# GSMMHMUltraSlim.net
KiCad netlist of a schematic drawn in Altium Designer
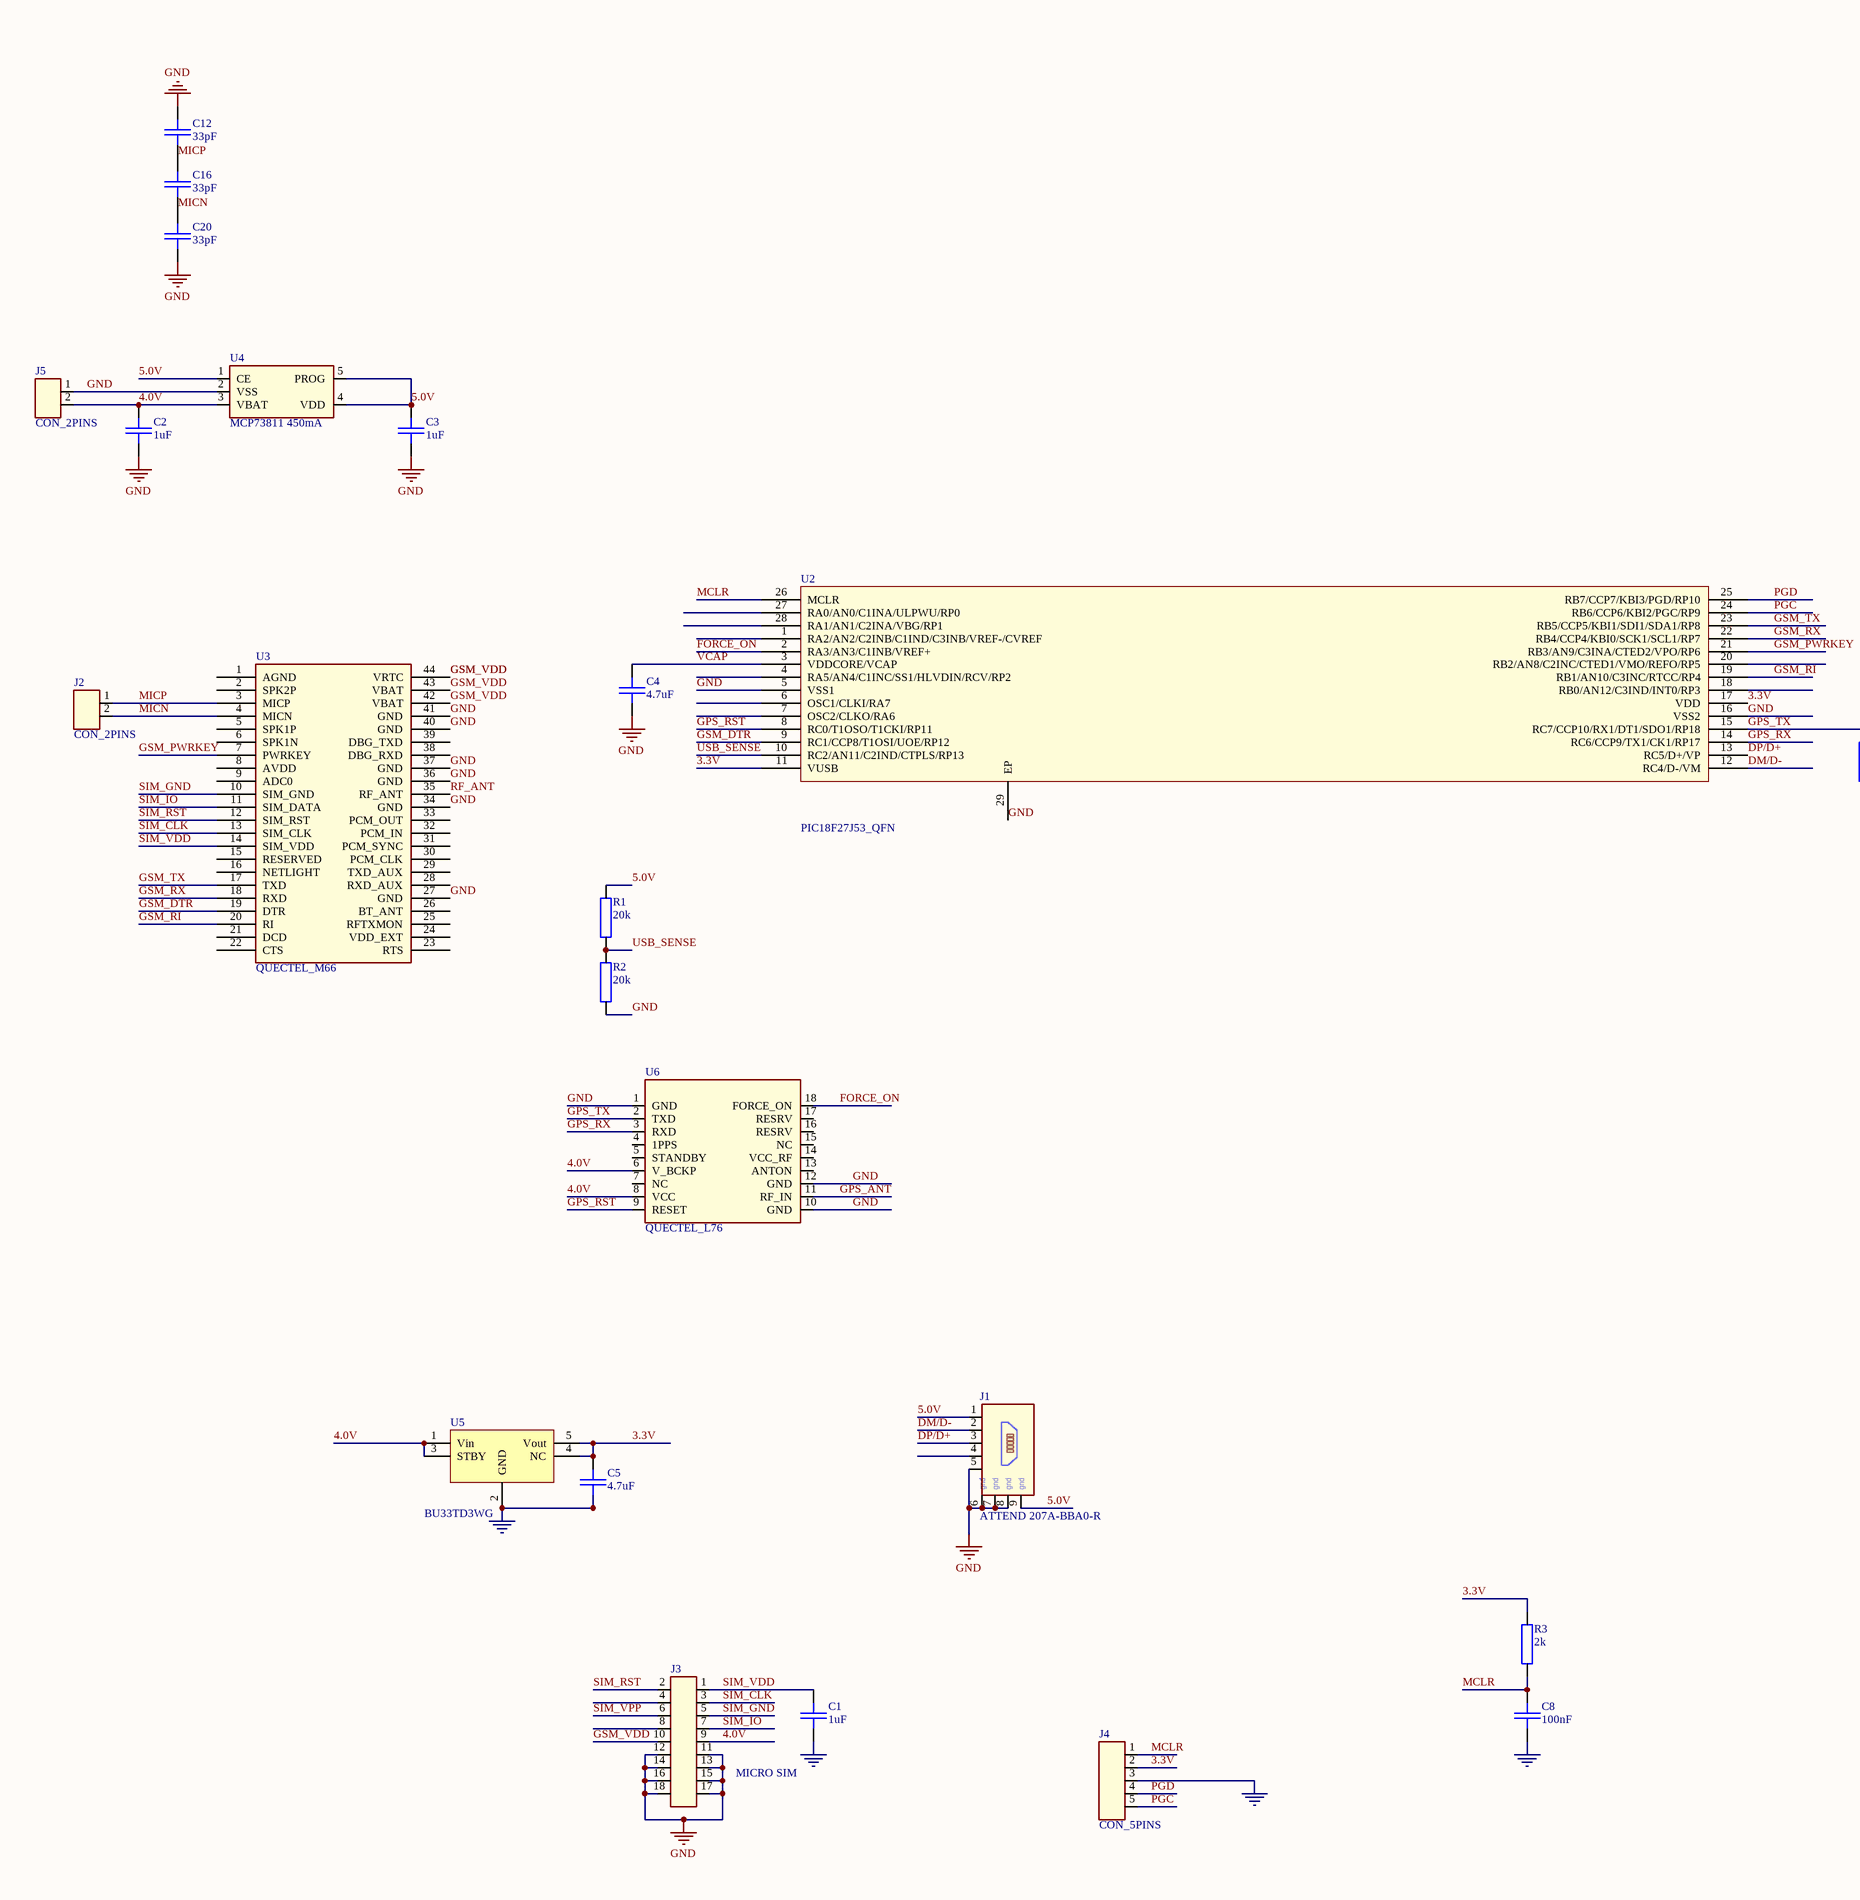
[diagram p0: GSMMHMUltraSlim.SchDoc, left]
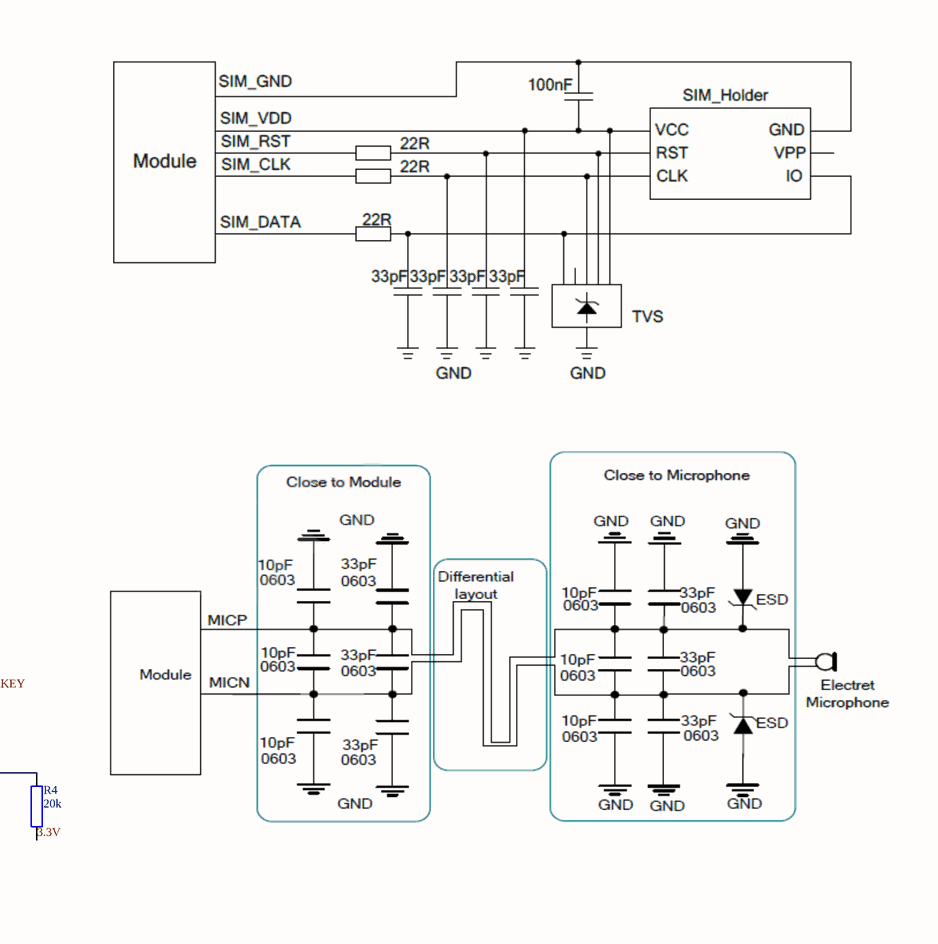
[diagram p1: GSMMHMUltraSlim.SchDoc, right]

(export (version "E")
  (design (tool "Eeschema 10.0.6"))
  (components
    (comp (ref "C1") (value "1uF") (footprint "SMD_0603_CAPC1608X95N") (libsource (lib "DLV") (part "C")))
    (comp (ref "C2") (value "1uF") (footprint "SMD_0603_CAPC1608X95N") (libsource (lib "DLV") (part "C")))
    (comp (ref "C3") (value "1uF") (footprint "SMD_0603_CAPC1608X95N") (libsource (lib "DLV") (part "C")))
    (comp (ref "C4") (value "4.7uF") (footprint "SMD_0603_CAPC1608X95N") (libsource (lib "DLV") (part "C")))
    (comp (ref "C5") (value "4.7uF") (footprint "SMD_0603_CAPC1608X95N") (libsource (lib "DLV") (part "C")))
    (comp (ref "C8") (value "100nF") (footprint "SMD_0603_CAPC1608X95N") (libsource (lib "DLV") (part "C")))
    (comp (ref "C12") (value "33pF") (footprint "SMD_0603_CAPC1608X95N") (libsource (lib "DLV") (part "C")))
    (comp (ref "C16") (value "33pF") (footprint "SMD_0603_CAPC1608X95N") (libsource (lib "DLV") (part "C")))
    (comp (ref "C20") (value "33pF") (footprint "SMD_0603_CAPC1608X95N") (libsource (lib "DLV") (part "C")))
    (comp (ref "J1")
      (value "ATTEND 207A-BBA0-R")
      (footprint "SMD_CON_MICRO_USB")
      (libsource (lib "DLV") (part "CON_USB_MINI"))
    )
    (comp (ref "J2") (value "CON_2PINS") (footprint "SMD_MIC_4MM") (libsource (lib "DLV") (part "CON_2PINS")))
    (comp (ref "J3")
      (value "MICRO SIM")
      (footprint "SMD_CON-WURTH_MICRO_SIM_693021010811")
      (libsource (lib "DLV") (part "CON_2ROWS_18PINS"))
    )
    (comp (ref "J4") (value "CON_5PINS") (footprint "SIP5 - PGM") (libsource (lib "DLV") (part "CON_5PINS")))
    (comp (ref "J5")
      (value "CON_2PINS")
      (footprint "PTH_HDRV02W64P254_1X02")
      (libsource (lib "DLV") (part "CON_2PINS"))
    )
    (comp (ref "R1") (value "20k") (footprint "SMD_0603_RESC1608X55N") (libsource (lib "DLV") (part "R")))
    (comp (ref "R2") (value "20k") (footprint "SMD_0603_RESC1608X55N") (libsource (lib "DLV") (part "R")))
    (comp (ref "R3") (value "2k") (footprint "SMD_0603_RESC1608X55N") (libsource (lib "DLV") (part "R")))
    (comp (ref "R4") (value "20k") (footprint "SMD_0603_RESC1608X55N") (libsource (lib "DLV") (part "R")))
    (comp (ref "U2")
      (value "PIC18F27J53_QFN")
      (footprint "SMD_QFN65P600X600X100-29AN")
      (libsource (lib "DLV") (part "IC_PIC18F27J53_QFN"))
    )
    (comp (ref "U3")
      (value "QUECTEL_M66")
      (footprint "SMD_MOD_M66-44N - NO UNUSED PINS")
      (libsource (lib "DLV") (part "MOD_QUECTEL_M66"))
    )
    (comp (ref "U4")
      (value "MCP73811 450mA")
      (footprint "SMD_SOT26_SOT95P285X140-5N - DLV")
      (description "MCP73812")
      (fields
        (field (name "DB_PART_NUMBER") "PSU000000127")
        (field (name "DB_MANUFACTURER_PART") "ROHM        BD33KA5WF-E2")
        (field (name "DB_APPROVED_BY") "VSN")
      )
      (libsource (lib "DLV") (part "IC_MCP73812"))
    )
    (comp (ref "U5")
      (value "BU33TD3WG")
      (footprint "SMD_SOT26_SOT95P285X140-5N - DLV")
      (libsource (lib "DLV") (part "IC_BU33TD3WG"))
    )
    (comp (ref "U6")
      (value "QUECTEL_L76")
      (footprint "SMD_MOD_L76_SOIC110P970X1010-18N - NO UNUSED PINS")
      (libsource (lib "DLV") (part "MOD_QUECTEL_L76"))
    )
  )
  (nets
    (net (code "1") (name "/3.3V") (class "Default")
      (node (ref "C5") (pin "1") (pinfunction "1_1") (pintype "passive"))
      (node (ref "J4") (pin "2") (pinfunction "2_2") (pintype "passive"))
      (node (ref "R3") (pin "1") (pinfunction "1_1") (pintype "passive"))
      (node (ref "R4") (pin "1") (pinfunction "1_1") (pintype "passive"))
      (node (ref "U2") (pin "11") (pinfunction "VUSB_11") (pintype "passive"))
      (node (ref "U2") (pin "17") (pinfunction "VDD_17") (pintype "passive"))
      (node (ref "U5") (pin "4") (pinfunction "NC_4") (pintype "passive"))
      (node (ref "U5") (pin "5") (pinfunction "Vout_5") (pintype "passive"))
    )
    (net (code "2") (name "/4.0V") (class "Default")
      (node (ref "C2") (pin "1") (pinfunction "1_1") (pintype "passive"))
      (node (ref "J3") (pin "9") (pinfunction "9_9") (pintype "passive"))
      (node (ref "J5") (pin "2") (pinfunction "2_2") (pintype "passive"))
      (node (ref "U4") (pin "3") (pinfunction "VBAT_3") (pintype "passive"))
      (node (ref "U5") (pin "1") (pinfunction "Vin_1") (pintype "passive"))
      (node (ref "U5") (pin "3") (pinfunction "STBY_3") (pintype "passive"))
      (node (ref "U6") (pin "6") (pinfunction "V_BCKP_6") (pintype "passive"))
      (node (ref "U6") (pin "8") (pinfunction "VCC_8") (pintype "passive"))
    )
    (net (code "3") (name "/5.0V") (class "Default")
      (node (ref "C3") (pin "1") (pinfunction "1_1") (pintype "passive"))
      (node (ref "J1") (pin "1") (pinfunction "1_1") (pintype "passive"))
      (node (ref "J1") (pin "9") (pinfunction "9_9") (pintype "passive"))
      (node (ref "R1") (pin "2") (pinfunction "2_2") (pintype "passive"))
      (node (ref "U4") (pin "1") (pinfunction "CE_1") (pintype "passive"))
      (node (ref "U4") (pin "4") (pinfunction "VDD_4") (pintype "passive"))
      (node (ref "U4") (pin "5") (pinfunction "PROG_5") (pintype "passive"))
    )
    (net (code "4") (name "/DM{slash}D-") (class "Default")
      (node (ref "J1") (pin "2") (pinfunction "2_2") (pintype "passive"))
      (node (ref "U2") (pin "12") (pinfunction "RC4/D-/VM_12") (pintype "passive"))
    )
    (net (code "5") (name "/DP{slash}D+") (class "Default")
      (node (ref "J1") (pin "3") (pinfunction "3_3") (pintype "passive"))
      (node (ref "U2") (pin "13") (pinfunction "RC5/D+/VP_13") (pintype "passive"))
    )
    (net (code "6") (name "/FORCE_ON") (class "Default")
      (node (ref "U2") (pin "2") (pinfunction "RA3/AN3/C1INB/VREF+_2") (pintype "passive"))
      (node (ref "U6") (pin "18") (pinfunction "FORCE_ON_18") (pintype "passive"))
    )
    (net (code "7") (name "/GPS_ANT") (class "Default")
      (node (ref "U6") (pin "11") (pinfunction "RF_IN_11") (pintype "passive"))
    )
    (net (code "8") (name "/GPS_RST") (class "Default")
      (node (ref "U2") (pin "8") (pinfunction "RC0/T1OSO/T1CKI/RP11_8") (pintype "passive"))
      (node (ref "U6") (pin "9") (pinfunction "RESET_9") (pintype "passive"))
    )
    (net (code "9") (name "/GPS_RX") (class "Default")
      (node (ref "U2") (pin "14") (pinfunction "RC6/CCP9/TX1/CK1/RP17_14") (pintype "passive"))
      (node (ref "U6") (pin "3") (pinfunction "RXD_3") (pintype "passive"))
    )
    (net (code "10") (name "/GPS_TX") (class "Default")
      (node (ref "R4") (pin "2") (pinfunction "2_2") (pintype "passive"))
      (node (ref "U2") (pin "15") (pinfunction "RC7/CCP10/RX1/DT1/SDO1/RP18_15") (pintype "passive"))
      (node (ref "U6") (pin "2") (pinfunction "TXD_2") (pintype "passive"))
    )
    (net (code "11") (name "/GSM_DTR") (class "Default")
      (node (ref "U2") (pin "9") (pinfunction "RC1/CCP8/T1OSI/UOE/RP12_9") (pintype "passive"))
      (node (ref "U3") (pin "19") (pinfunction "DTR_19") (pintype "passive"))
    )
    (net (code "12") (name "/GSM_PWRKEY") (class "Default")
      (node (ref "U2") (pin "21") (pinfunction "RB3/AN9/C3INA/CTED2/VPO/RP6_21") (pintype "passive"))
      (node (ref "U3") (pin "7") (pinfunction "PWRKEY_7") (pintype "passive"))
    )
    (net (code "13") (name "/GSM_RI") (class "Default")
      (node (ref "U2") (pin "19") (pinfunction "RB1/AN10/C3INC/RTCC/RP4_19") (pintype "passive"))
      (node (ref "U3") (pin "20") (pinfunction "RI_20") (pintype "passive"))
    )
    (net (code "14") (name "/GSM_RX") (class "Default")
      (node (ref "U2") (pin "22") (pinfunction "RB4/CCP4/KBI0/SCK1/SCL1/RP7_22") (pintype "passive"))
      (node (ref "U3") (pin "18") (pinfunction "RXD_18") (pintype "passive"))
    )
    (net (code "15") (name "/GSM_TX") (class "Default")
      (node (ref "U2") (pin "23") (pinfunction "RB5/CCP5/KBI1/SDI1/SDA1/RP8_23") (pintype "passive"))
      (node (ref "U3") (pin "17") (pinfunction "TXD_17") (pintype "passive"))
    )
    (net (code "16") (name "/GSM_VDD") (class "Default")
      (node (ref "J3") (pin "10") (pinfunction "10_10") (pintype "passive"))
      (node (ref "U3") (pin "42") (pinfunction "VBAT_42") (pintype "passive"))
      (node (ref "U3") (pin "43") (pinfunction "VBAT_43") (pintype "passive"))
      (node (ref "U3") (pin "44") (pinfunction "VRTC_44") (pintype "passive"))
    )
    (net (code "17") (name "/MCLR") (class "Default")
      (node (ref "C8") (pin "1") (pinfunction "1_1") (pintype "passive"))
      (node (ref "J4") (pin "1") (pinfunction "1_1") (pintype "passive"))
      (node (ref "R3") (pin "2") (pinfunction "2_2") (pintype "passive"))
      (node (ref "U2") (pin "26") (pinfunction "MCLR_26") (pintype "passive"))
    )
    (net (code "18") (name "/MICN") (class "Default")
      (node (ref "C16") (pin "2") (pinfunction "2_2") (pintype "passive"))
      (node (ref "C20") (pin "1") (pinfunction "1_1") (pintype "passive"))
      (node (ref "J2") (pin "2") (pinfunction "2_2") (pintype "passive"))
      (node (ref "U3") (pin "4") (pinfunction "MICN_4") (pintype "passive"))
    )
    (net (code "19") (name "/MICP") (class "Default")
      (node (ref "C12") (pin "2") (pinfunction "2_2") (pintype "passive"))
      (node (ref "C16") (pin "1") (pinfunction "1_1") (pintype "passive"))
      (node (ref "J2") (pin "1") (pinfunction "1_1") (pintype "passive"))
      (node (ref "U3") (pin "3") (pinfunction "MICP_3") (pintype "passive"))
    )
    (net (code "20") (name "/PGC") (class "Default")
      (node (ref "J4") (pin "5") (pinfunction "5_5") (pintype "passive"))
      (node (ref "U2") (pin "24") (pinfunction "RB6/CCP6/KBI2/PGC/RP9_24") (pintype "passive"))
    )
    (net (code "21") (name "/PGD") (class "Default")
      (node (ref "J4") (pin "4") (pinfunction "4_4") (pintype "passive"))
      (node (ref "U2") (pin "25") (pinfunction "RB7/CCP7/KBI3/PGD/RP10_25") (pintype "passive"))
    )
    (net (code "22") (name "/RF_ANT") (class "Default")
      (node (ref "U3") (pin "35") (pinfunction "RF_ANT_35") (pintype "passive"))
    )
    (net (code "23") (name "/SIM_CLK") (class "Default")
      (node (ref "J3") (pin "3") (pinfunction "3_3") (pintype "passive"))
      (node (ref "U3") (pin "13") (pinfunction "SIM_CLK_13") (pintype "passive"))
    )
    (net (code "24") (name "/SIM_GND") (class "Default")
      (node (ref "J3") (pin "5") (pinfunction "5_5") (pintype "passive"))
      (node (ref "U3") (pin "10") (pinfunction "SIM_GND_10") (pintype "passive"))
    )
    (net (code "25") (name "/SIM_IO") (class "Default")
      (node (ref "J3") (pin "7") (pinfunction "7_7") (pintype "passive"))
      (node (ref "U3") (pin "11") (pinfunction "SIM_DATA_11") (pintype "passive"))
    )
    (net (code "26") (name "/SIM_RST") (class "Default")
      (node (ref "J3") (pin "2") (pinfunction "2_2") (pintype "passive"))
      (node (ref "U3") (pin "12") (pinfunction "SIM_RST_12") (pintype "passive"))
    )
    (net (code "27") (name "/SIM_VDD") (class "Default")
      (node (ref "C1") (pin "1") (pinfunction "1_1") (pintype "passive"))
      (node (ref "J3") (pin "1") (pinfunction "1_1") (pintype "passive"))
      (node (ref "U3") (pin "14") (pinfunction "SIM_VDD_14") (pintype "passive"))
    )
    (net (code "28") (name "/SIM_VPP") (class "Default")
      (node (ref "J3") (pin "6") (pinfunction "6_6") (pintype "passive"))
    )
    (net (code "29") (name "/USB_SENSE") (class "Default")
      (node (ref "R1") (pin "1") (pinfunction "1_1") (pintype "passive"))
      (node (ref "R2") (pin "2") (pinfunction "2_2") (pintype "passive"))
      (node (ref "U2") (pin "10") (pinfunction "RC2/AN11/C2IND/CTPLS/RP13_10") (pintype "passive"))
    )
    (net (code "30") (name "/VCAP") (class "Default")
      (node (ref "C4") (pin "1") (pinfunction "1_1") (pintype "passive"))
      (node (ref "U2") (pin "3") (pinfunction "VDDCORE/VCAP_3") (pintype "passive"))
    )
    (net (code "31") (name "GND") (class "Default")
      (node (ref "C1") (pin "2") (pinfunction "2_2") (pintype "passive"))
      (node (ref "C12") (pin "1") (pinfunction "1_1") (pintype "passive"))
      (node (ref "C2") (pin "2") (pinfunction "2_2") (pintype "passive"))
      (node (ref "C20") (pin "2") (pinfunction "2_2") (pintype "passive"))
      (node (ref "C3") (pin "2") (pinfunction "2_2") (pintype "passive"))
      (node (ref "C4") (pin "2") (pinfunction "2_2") (pintype "passive"))
      (node (ref "C5") (pin "2") (pinfunction "2_2") (pintype "passive"))
      (node (ref "C8") (pin "2") (pinfunction "2_2") (pintype "passive"))
      (node (ref "J1") (pin "5") (pinfunction "5_5") (pintype "passive"))
      (node (ref "J1") (pin "6") (pinfunction "6_6") (pintype "passive"))
      (node (ref "J1") (pin "7") (pinfunction "7_7") (pintype "passive"))
      (node (ref "J1") (pin "8") (pinfunction "8_8") (pintype "passive"))
      (node (ref "J3") (pin "11") (pinfunction "11_11") (pintype "passive"))
      (node (ref "J3") (pin "12") (pinfunction "12_12") (pintype "passive"))
      (node (ref "J3") (pin "13") (pinfunction "13_13") (pintype "passive"))
      (node (ref "J3") (pin "14") (pinfunction "14_14") (pintype "passive"))
      (node (ref "J3") (pin "15") (pinfunction "15_15") (pintype "passive"))
      (node (ref "J3") (pin "16") (pinfunction "16_16") (pintype "passive"))
      (node (ref "J3") (pin "17") (pinfunction "17_17") (pintype "passive"))
      (node (ref "J3") (pin "18") (pinfunction "18_18") (pintype "passive"))
      (node (ref "J4") (pin "3") (pinfunction "3_3") (pintype "passive"))
      (node (ref "J5") (pin "1") (pinfunction "1_1") (pintype "passive"))
      (node (ref "R2") (pin "1") (pinfunction "1_1") (pintype "passive"))
      (node (ref "U2") (pin "16") (pinfunction "VSS2_16") (pintype "passive"))
      (node (ref "U2") (pin "29") (pinfunction "EP_29") (pintype "passive"))
      (node (ref "U2") (pin "5") (pinfunction "VSS1_5") (pintype "passive"))
      (node (ref "U3") (pin "27") (pinfunction "GND_27") (pintype "passive"))
      (node (ref "U3") (pin "34") (pinfunction "GND_34") (pintype "passive"))
      (node (ref "U3") (pin "36") (pinfunction "GND_36") (pintype "passive"))
      (node (ref "U3") (pin "37") (pinfunction "GND_37") (pintype "passive"))
      (node (ref "U3") (pin "40") (pinfunction "GND_40") (pintype "passive"))
      (node (ref "U3") (pin "41") (pinfunction "GND_41") (pintype "passive"))
      (node (ref "U4") (pin "2") (pinfunction "VSS_2") (pintype "passive"))
      (node (ref "U5") (pin "2") (pinfunction "GND_2") (pintype "passive"))
      (node (ref "U6") (pin "1") (pinfunction "GND_1") (pintype "passive"))
      (node (ref "U6") (pin "10") (pinfunction "GND_10") (pintype "passive"))
      (node (ref "U6") (pin "12") (pinfunction "GND_12") (pintype "passive"))
    )
    (net (code "32") (name "unconnected-(J1-Pad4)") (class "Default")
      (node (ref "J1") (pin "4") (pinfunction "4_4") (pintype "passive"))
    )
    (net (code "33") (name "unconnected-(J3-Pad4)") (class "Default")
      (node (ref "J3") (pin "4") (pinfunction "4_4") (pintype "passive"))
    )
    (net (code "34") (name "unconnected-(J3-Pad8)") (class "Default")
      (node (ref "J3") (pin "8") (pinfunction "8_8") (pintype "passive"))
    )
    (net (code "35") (name "unconnected-(U2-OSC1{slash}CLKI{slash}RA7-Pad6)") (class "Default")
      (node (ref "U2") (pin "6") (pinfunction "OSC1/CLKI/RA7_6") (pintype "passive"))
    )
    (net (code "36") (name "unconnected-(U2-OSC2{slash}CLKO{slash}RA6-Pad7)") (class "Default")
      (node (ref "U2") (pin "7") (pinfunction "OSC2/CLKO/RA6_7") (pintype "passive"))
    )
    (net (code "37") (name "unconnected-(U2-RA0{slash}AN0{slash}C1INA{slash}ULPWU{slash}RP0-Pad27)") (class "Default")
      (node (ref "U2") (pin "27") (pinfunction "RA0/AN0/C1INA/ULPWU/RP0_27") (pintype "passive"))
    )
    (net (code "38") (name "unconnected-(U2-RA1{slash}AN1{slash}C2INA{slash}VBG{slash}RP1-Pad28)") (class "Default")
      (node (ref "U2") (pin "28") (pinfunction "RA1/AN1/C2INA/VBG/RP1_28") (pintype "passive"))
    )
    (net (code "39") (name "unconnected-(U2-RA2{slash}AN2{slash}C2INB{slash}C1IND{slash}C3INB{slash}VREF-{slash}CVREF-Pad1)") (class "Default")
      (node (ref "U2") (pin "1") (pinfunction "RA2/AN2/C2INB/C1IND/C3INB/VREF-/CVREF_1") (pintype "passive"))
    )
    (net (code "40") (name "unconnected-(U2-RA5{slash}AN4{slash}C1INC{slash}SS1{slash}HLVDIN{slash}RCV{slash}RP2-Pad4)") (class "Default")
      (node (ref "U2") (pin "4") (pinfunction "RA5/AN4/C1INC/SS1/HLVDIN/RCV/RP2_4") (pintype "passive"))
    )
    (net (code "41") (name "unconnected-(U2-RB0{slash}AN12{slash}C3IND{slash}INT0{slash}RP3-Pad18)") (class "Default")
      (node (ref "U2") (pin "18") (pinfunction "RB0/AN12/C3IND/INT0/RP3_18") (pintype "passive"))
    )
    (net (code "42") (name "unconnected-(U2-RB2{slash}AN8{slash}C2INC{slash}CTED1{slash}VMO{slash}REFO{slash}RP5-Pad20)") (class "Default")
      (node (ref "U2") (pin "20") (pinfunction "RB2/AN8/C2INC/CTED1/VMO/REFO/RP5_20") (pintype "passive"))
    )
    (net (code "43") (name "unconnected-(U3-ADC0-Pad9)") (class "Default")
      (node (ref "U3") (pin "9") (pinfunction "ADC0_9") (pintype "passive"))
    )
    (net (code "44") (name "unconnected-(U3-AGND-Pad1)") (class "Default")
      (node (ref "U3") (pin "1") (pinfunction "AGND_1") (pintype "passive"))
    )
    (net (code "45") (name "unconnected-(U3-AVDD-Pad8)") (class "Default")
      (node (ref "U3") (pin "8") (pinfunction "AVDD_8") (pintype "passive"))
    )
    (net (code "46") (name "unconnected-(U3-BT_ANT-Pad26)") (class "Default")
      (node (ref "U3") (pin "26") (pinfunction "BT_ANT_26") (pintype "passive"))
    )
    (net (code "47") (name "unconnected-(U3-CTS-Pad22)") (class "Default")
      (node (ref "U3") (pin "22") (pinfunction "CTS_22") (pintype "passive"))
    )
    (net (code "48") (name "unconnected-(U3-DBG_RXD-Pad38)") (class "Default")
      (node (ref "U3") (pin "38") (pinfunction "DBG_RXD_38") (pintype "passive"))
    )
    (net (code "49") (name "unconnected-(U3-DBG_TXD-Pad39)") (class "Default")
      (node (ref "U3") (pin "39") (pinfunction "DBG_TXD_39") (pintype "passive"))
    )
    (net (code "50") (name "unconnected-(U3-DCD-Pad21)") (class "Default")
      (node (ref "U3") (pin "21") (pinfunction "DCD_21") (pintype "passive"))
    )
    (net (code "51") (name "unconnected-(U3-NETLIGHT-Pad16)") (class "Default")
      (node (ref "U3") (pin "16") (pinfunction "NETLIGHT_16") (pintype "passive"))
    )
    (net (code "52") (name "unconnected-(U3-PCM_CLK-Pad30)") (class "Default")
      (node (ref "U3") (pin "30") (pinfunction "PCM_CLK_30") (pintype "passive"))
    )
    (net (code "53") (name "unconnected-(U3-PCM_IN-Pad32)") (class "Default")
      (node (ref "U3") (pin "32") (pinfunction "PCM_IN_32") (pintype "passive"))
    )
    (net (code "54") (name "unconnected-(U3-PCM_OUT-Pad33)") (class "Default")
      (node (ref "U3") (pin "33") (pinfunction "PCM_OUT_33") (pintype "passive"))
    )
    (net (code "55") (name "unconnected-(U3-PCM_SYNC-Pad31)") (class "Default")
      (node (ref "U3") (pin "31") (pinfunction "PCM_SYNC_31") (pintype "passive"))
    )
    (net (code "56") (name "unconnected-(U3-RESERVED-Pad15)") (class "Default")
      (node (ref "U3") (pin "15") (pinfunction "RESERVED_15") (pintype "passive"))
    )
    (net (code "57") (name "unconnected-(U3-RFTXMON-Pad25)") (class "Default")
      (node (ref "U3") (pin "25") (pinfunction "RFTXMON_25") (pintype "passive"))
    )
    (net (code "58") (name "unconnected-(U3-RTS-Pad23)") (class "Default")
      (node (ref "U3") (pin "23") (pinfunction "RTS_23") (pintype "passive"))
    )
    (net (code "59") (name "unconnected-(U3-RXD_AUX-Pad28)") (class "Default")
      (node (ref "U3") (pin "28") (pinfunction "RXD_AUX_28") (pintype "passive"))
    )
    (net (code "60") (name "unconnected-(U3-SPK1N-Pad6)") (class "Default")
      (node (ref "U3") (pin "6") (pinfunction "SPK1N_6") (pintype "passive"))
    )
    (net (code "61") (name "unconnected-(U3-SPK1P-Pad5)") (class "Default")
      (node (ref "U3") (pin "5") (pinfunction "SPK1P_5") (pintype "passive"))
    )
    (net (code "62") (name "unconnected-(U3-SPK2P-Pad2)") (class "Default")
      (node (ref "U3") (pin "2") (pinfunction "SPK2P_2") (pintype "passive"))
    )
    (net (code "63") (name "unconnected-(U3-TXD_AUX-Pad29)") (class "Default")
      (node (ref "U3") (pin "29") (pinfunction "TXD_AUX_29") (pintype "passive"))
    )
    (net (code "64") (name "unconnected-(U3-VDD_EXT-Pad24)") (class "Default")
      (node (ref "U3") (pin "24") (pinfunction "VDD_EXT_24") (pintype "passive"))
    )
    (net (code "65") (name "unconnected-(U6-1PPS-Pad4)") (class "Default")
      (node (ref "U6") (pin "4") (pinfunction "1PPS_4") (pintype "passive"))
    )
    (net (code "66") (name "unconnected-(U6-ANTON-Pad13)") (class "Default")
      (node (ref "U6") (pin "13") (pinfunction "ANTON_13") (pintype "passive"))
    )
    (net (code "67") (name "unconnected-(U6-NC-Pad7)") (class "Default")
      (node (ref "U6") (pin "7") (pinfunction "NC_7") (pintype "passive"))
    )
    (net (code "68") (name "unconnected-(U6-NC-Pad15)") (class "Default")
      (node (ref "U6") (pin "15") (pinfunction "NC_15") (pintype "passive"))
    )
    (net (code "69") (name "unconnected-(U6-RESRV-Pad16)") (class "Default")
      (node (ref "U6") (pin "16") (pinfunction "RESRV_16") (pintype "passive"))
    )
    (net (code "70") (name "unconnected-(U6-RESRV-Pad17)") (class "Default")
      (node (ref "U6") (pin "17") (pinfunction "RESRV_17") (pintype "passive"))
    )
    (net (code "71") (name "unconnected-(U6-STANDBY-Pad5)") (class "Default")
      (node (ref "U6") (pin "5") (pinfunction "STANDBY_5") (pintype "passive"))
    )
    (net (code "72") (name "unconnected-(U6-VCC_RF-Pad14)") (class "Default")
      (node (ref "U6") (pin "14") (pinfunction "VCC_RF_14") (pintype "passive"))
    )
  )
)
